# Main_V3.net
KiCad netlist of a schematic drawn in EAGLE
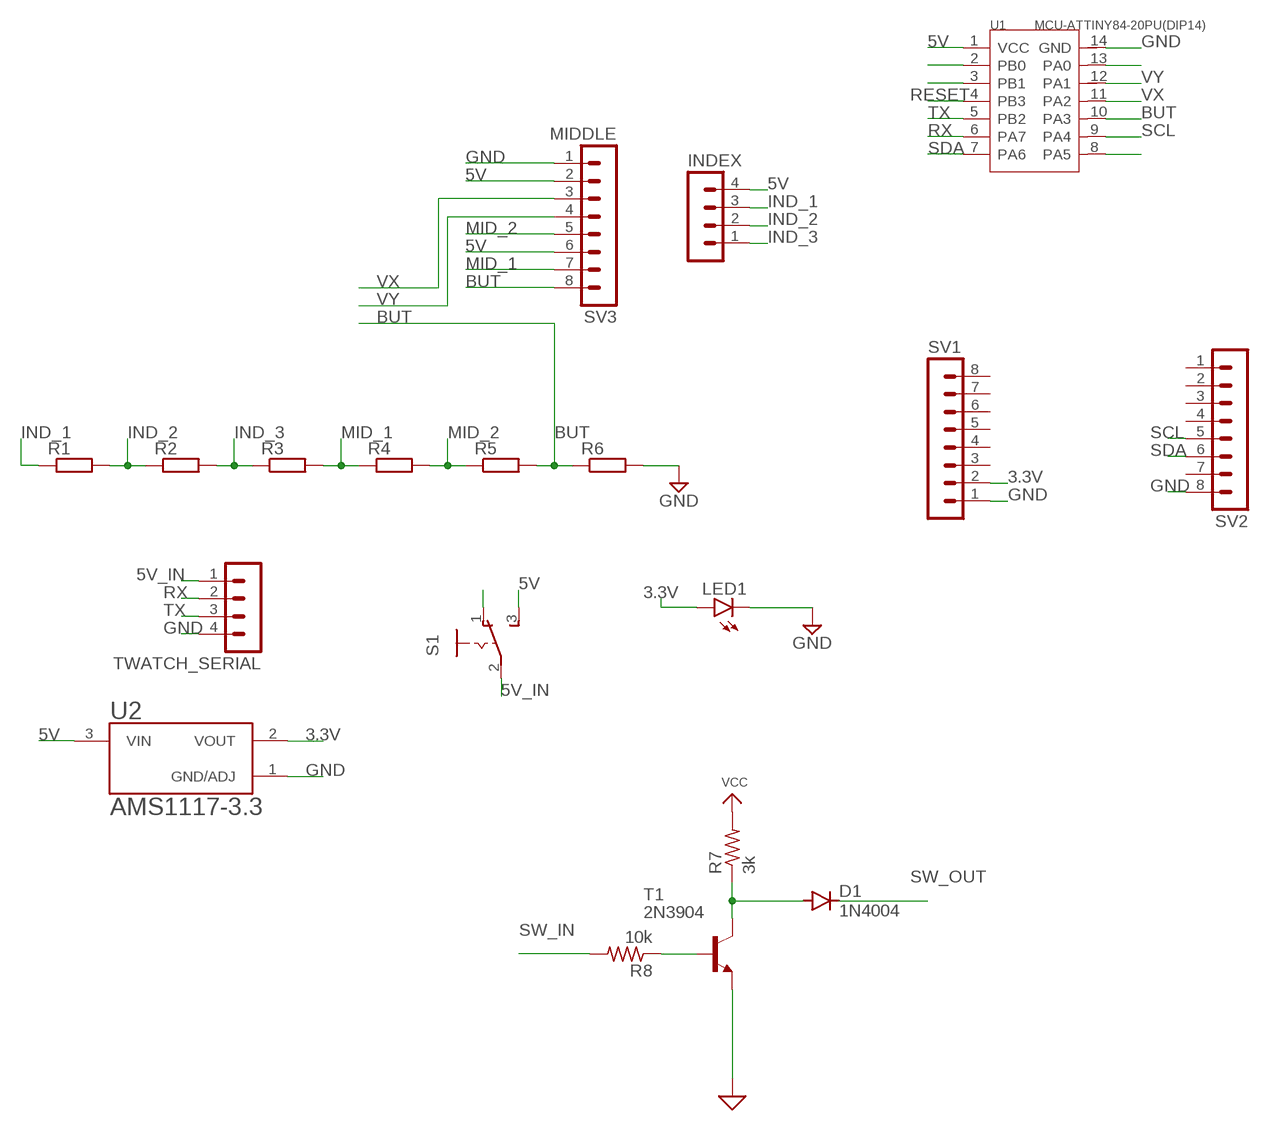
[diagram p0: schematic, sheet 1]

(export (version "E")
  (design (tool "Eeschema 10.0.6"))
  (components
    (comp (ref "D1")
      (value "1N4004")
      (footprint "eagle-import:DO41-10")
      (libsource (lib "eagle-import") (part "1N4004"))
    )
    (comp (ref "INDEX")
      (value "MA04-1")
      (footprint "eagle-import:MA04-1")
      (libsource (lib "eagle-import") (part "MA04-1"))
    )
    (comp (ref "LED1")
      (value "LED5MM")
      (footprint "eagle-import:LED5MM")
      (libsource (lib "eagle-import") (part "LED5MM"))
    )
    (comp (ref "R1")
      (value "R-EU_0204/7")
      (footprint "eagle-import:0204_7")
      (libsource (lib "eagle-import") (part "R-EU_0204/7"))
    )
    (comp (ref "R2")
      (value "R-EU_0204/7")
      (footprint "eagle-import:0204_7")
      (libsource (lib "eagle-import") (part "R-EU_0204/7"))
    )
    (comp (ref "R3")
      (value "R-EU_0204/7")
      (footprint "eagle-import:0204_7")
      (libsource (lib "eagle-import") (part "R-EU_0204/7"))
    )
    (comp (ref "R4")
      (value "R-EU_0204/7")
      (footprint "eagle-import:0204_7")
      (libsource (lib "eagle-import") (part "R-EU_0204/7"))
    )
    (comp (ref "R5")
      (value "R-EU_0204/7")
      (footprint "eagle-import:0204_7")
      (libsource (lib "eagle-import") (part "R-EU_0204/7"))
    )
    (comp (ref "R6")
      (value "R-EU_0204/7")
      (footprint "eagle-import:0204_7")
      (libsource (lib "eagle-import") (part "R-EU_0204/7"))
    )
    (comp (ref "R7")
      (value "3k")
      (footprint "eagle-import:0204_5")
      (libsource (lib "eagle-import") (part "R-US_0204/5"))
    )
    (comp (ref "R8")
      (value "10k")
      (footprint "eagle-import:0204_5")
      (libsource (lib "eagle-import") (part "R-US_0204/5"))
    )
    (comp (ref "S1")
      (value "255SB")
      (footprint "eagle-import:255SB")
      (libsource (lib "eagle-import") (part "255SB"))
    )
    (comp (ref "SV1")
      (value "MA08-1")
      (footprint "eagle-import:MA08-1")
      (libsource (lib "eagle-import") (part "MA08-1"))
    )
    (comp (ref "SV2")
      (value "MA08-1")
      (footprint "eagle-import:MA08-1")
      (libsource (lib "eagle-import") (part "MA08-1"))
    )
    (comp (ref "SV3")
      (value "MIDDLE")
      (footprint "eagle-import:MA08-1")
      (libsource (lib "eagle-import") (part "MA08-1"))
    )
    (comp (ref "T1")
      (value "2N3904")
      (footprint "eagle-import:TO92")
      (libsource (lib "eagle-import") (part "2N3904"))
    )
    (comp (ref "TWATCH_SERIAL")
      (value "MA04-1")
      (footprint "eagle-import:MA04-1")
      (libsource (lib "eagle-import") (part "MA04-1"))
    )
    (comp (ref "U1")
      (value "MCU-ATTINY84-20PU(DIP14)")
      (footprint "eagle-import:DIP14-2.54-17.24X6.35MM")
      (fields (field (name "MF") "Microchip") (field (name "MP") "ATTINY84-20PU"))
      (libsource (lib "eagle-import") (part "MCU-ATTINY84-20PU(DIP14)"))
    )
    (comp (ref "U2")
      (value "AMS1117-3.3")
      (footprint "eagle-import:SOT229P700X180-4N")
      (fields (field (name "MF") "Advanced Monolithic Systems"))
      (libsource (lib "eagle-import") (part "AMS1117-3.3"))
    )
  )
  (nets
    (net (code "1") (name "/3.3V") (class "Default")
      (node (ref "LED1") (pin "A") (pinfunction "A_A") (pintype "passive"))
      (node (ref "SV1") (pin "2") (pinfunction "2_2") (pintype "passive"))
      (node (ref "U2") (pin "2") (pinfunction "VOUT_2") (pintype "output"))
    )
    (net (code "2") (name "/5V") (class "Default")
      (node (ref "INDEX") (pin "4") (pinfunction "4_4") (pintype "passive"))
      (node (ref "S1") (pin "3") (pinfunction "S_3") (pintype "passive"))
      (node (ref "SV3") (pin "2") (pinfunction "2_2") (pintype "passive"))
      (node (ref "SV3") (pin "6") (pinfunction "6_6") (pintype "passive"))
      (node (ref "U1") (pin "1") (pinfunction "VCC_1") (pintype "bidirectional"))
      (node (ref "U2") (pin "3") (pinfunction "VIN_3") (pintype "input"))
    )
    (net (code "3") (name "/5V_IN") (class "Default")
      (node (ref "S1") (pin "2") (pinfunction "P_2") (pintype "passive"))
      (node (ref "TWATCH_SERIAL") (pin "1") (pinfunction "1_1") (pintype "passive"))
    )
    (net (code "4") (name "/BUT") (class "Default")
      (node (ref "R5") (pin "2") (pinfunction "2_2") (pintype "passive"))
      (node (ref "R6") (pin "1") (pinfunction "1_1") (pintype "passive"))
      (node (ref "SV3") (pin "8") (pinfunction "8_8") (pintype "passive"))
      (node (ref "U1") (pin "10") (pinfunction "PA3_10") (pintype "bidirectional"))
    )
    (net (code "5") (name "/IND_1") (class "Default")
      (node (ref "INDEX") (pin "3") (pinfunction "3_3") (pintype "passive"))
      (node (ref "R1") (pin "1") (pinfunction "1_1") (pintype "passive"))
    )
    (net (code "6") (name "/IND_2") (class "Default")
      (node (ref "INDEX") (pin "2") (pinfunction "2_2") (pintype "passive"))
      (node (ref "R1") (pin "2") (pinfunction "2_2") (pintype "passive"))
      (node (ref "R2") (pin "1") (pinfunction "1_1") (pintype "passive"))
    )
    (net (code "7") (name "/IND_3") (class "Default")
      (node (ref "INDEX") (pin "1") (pinfunction "1_1") (pintype "passive"))
      (node (ref "R2") (pin "2") (pinfunction "2_2") (pintype "passive"))
      (node (ref "R3") (pin "1") (pinfunction "1_1") (pintype "passive"))
    )
    (net (code "8") (name "/MID_1") (class "Default")
      (node (ref "R3") (pin "2") (pinfunction "2_2") (pintype "passive"))
      (node (ref "R4") (pin "1") (pinfunction "1_1") (pintype "passive"))
      (node (ref "SV3") (pin "7") (pinfunction "7_7") (pintype "passive"))
    )
    (net (code "9") (name "/MID_2") (class "Default")
      (node (ref "R4") (pin "2") (pinfunction "2_2") (pintype "passive"))
      (node (ref "R5") (pin "1") (pinfunction "1_1") (pintype "passive"))
      (node (ref "SV3") (pin "5") (pinfunction "5_5") (pintype "passive"))
    )
    (net (code "10") (name "/RESET") (class "Default")
      (node (ref "U1") (pin "4") (pinfunction "PB3_4") (pintype "bidirectional"))
    )
    (net (code "11") (name "/RX") (class "Default")
      (node (ref "TWATCH_SERIAL") (pin "2") (pinfunction "2_2") (pintype "passive"))
      (node (ref "U1") (pin "6") (pinfunction "PA7_6") (pintype "bidirectional"))
    )
    (net (code "12") (name "/SCL") (class "Default")
      (node (ref "SV2") (pin "5") (pinfunction "5_5") (pintype "passive"))
      (node (ref "U1") (pin "9") (pinfunction "PA4_9") (pintype "bidirectional"))
    )
    (net (code "13") (name "/SDA") (class "Default")
      (node (ref "SV2") (pin "6") (pinfunction "6_6") (pintype "passive"))
      (node (ref "U1") (pin "7") (pinfunction "PA6_7") (pintype "bidirectional"))
    )
    (net (code "14") (name "/SW_IN") (class "Default")
      (node (ref "R8") (pin "2") (pinfunction "2_2") (pintype "passive"))
    )
    (net (code "15") (name "/SW_OUT") (class "Default")
      (node (ref "D1") (pin "C") (pinfunction "C_C") (pintype "passive"))
    )
    (net (code "16") (name "/TX") (class "Default")
      (node (ref "TWATCH_SERIAL") (pin "3") (pinfunction "3_3") (pintype "passive"))
      (node (ref "U1") (pin "5") (pinfunction "PB2_5") (pintype "bidirectional"))
    )
    (net (code "17") (name "/VX") (class "Default")
      (node (ref "SV3") (pin "3") (pinfunction "3_3") (pintype "passive"))
      (node (ref "U1") (pin "11") (pinfunction "PA2_11") (pintype "bidirectional"))
    )
    (net (code "18") (name "/VY") (class "Default")
      (node (ref "SV3") (pin "4") (pinfunction "4_4") (pintype "passive"))
      (node (ref "U1") (pin "12") (pinfunction "PA1_12") (pintype "bidirectional"))
    )
    (net (code "19") (name "GND") (class "Default")
      (node (ref "LED1") (pin "K") (pinfunction "C_K") (pintype "passive"))
      (node (ref "R6") (pin "2") (pinfunction "2_2") (pintype "passive"))
      (node (ref "SV1") (pin "1") (pinfunction "1_1") (pintype "passive"))
      (node (ref "SV2") (pin "8") (pinfunction "8_8") (pintype "passive"))
      (node (ref "SV3") (pin "1") (pinfunction "1_1") (pintype "passive"))
      (node (ref "T1") (pin "3") (pinfunction "E_3") (pintype "passive"))
      (node (ref "TWATCH_SERIAL") (pin "4") (pinfunction "4_4") (pintype "passive"))
      (node (ref "U1") (pin "14") (pinfunction "GND_14") (pintype "bidirectional"))
      (node (ref "U2") (pin "1") (pinfunction "GND/ADJ_1") (pintype "power_in"))
    )
    (net (code "20") (name "Net-(T1-B)") (class "Default")
      (node (ref "R8") (pin "1") (pinfunction "1_1") (pintype "passive"))
      (node (ref "T1") (pin "2") (pinfunction "B_2") (pintype "passive"))
    )
    (net (code "21") (name "Net-(T1-C)") (class "Default")
      (node (ref "D1") (pin "A") (pinfunction "A_A") (pintype "passive"))
      (node (ref "R7") (pin "1") (pinfunction "1_1") (pintype "passive"))
      (node (ref "T1") (pin "1") (pinfunction "C_1") (pintype "passive"))
    )
    (net (code "22") (name "VCC") (class "Default")
      (node (ref "R7") (pin "2") (pinfunction "2_2") (pintype "passive"))
    )
    (net (code "23") (name "unconnected-(S1-O-Pad1)") (class "Default")
      (node (ref "S1") (pin "1") (pinfunction "O_1") (pintype "passive"))
    )
    (net (code "24") (name "unconnected-(SV1-Pad3)") (class "Default")
      (node (ref "SV1") (pin "3") (pinfunction "3_3") (pintype "passive"))
    )
    (net (code "25") (name "unconnected-(SV1-Pad4)") (class "Default")
      (node (ref "SV1") (pin "4") (pinfunction "4_4") (pintype "passive"))
    )
    (net (code "26") (name "unconnected-(SV1-Pad5)") (class "Default")
      (node (ref "SV1") (pin "5") (pinfunction "5_5") (pintype "passive"))
    )
    (net (code "27") (name "unconnected-(SV1-Pad6)") (class "Default")
      (node (ref "SV1") (pin "6") (pinfunction "6_6") (pintype "passive"))
    )
    (net (code "28") (name "unconnected-(SV1-Pad7)") (class "Default")
      (node (ref "SV1") (pin "7") (pinfunction "7_7") (pintype "passive"))
    )
    (net (code "29") (name "unconnected-(SV1-Pad8)") (class "Default")
      (node (ref "SV1") (pin "8") (pinfunction "8_8") (pintype "passive"))
    )
    (net (code "30") (name "unconnected-(SV2-Pad1)") (class "Default")
      (node (ref "SV2") (pin "1") (pinfunction "1_1") (pintype "passive"))
    )
    (net (code "31") (name "unconnected-(SV2-Pad2)") (class "Default")
      (node (ref "SV2") (pin "2") (pinfunction "2_2") (pintype "passive"))
    )
    (net (code "32") (name "unconnected-(SV2-Pad3)") (class "Default")
      (node (ref "SV2") (pin "3") (pinfunction "3_3") (pintype "passive"))
    )
    (net (code "33") (name "unconnected-(SV2-Pad4)") (class "Default")
      (node (ref "SV2") (pin "4") (pinfunction "4_4") (pintype "passive"))
    )
    (net (code "34") (name "unconnected-(SV2-Pad7)") (class "Default")
      (node (ref "SV2") (pin "7") (pinfunction "7_7") (pintype "passive"))
    )
    (net (code "35") (name "unconnected-(U1-PA0-Pad13)") (class "Default")
      (node (ref "U1") (pin "13") (pinfunction "PA0_13") (pintype "bidirectional"))
    )
    (net (code "36") (name "unconnected-(U1-PA5-Pad8)") (class "Default")
      (node (ref "U1") (pin "8") (pinfunction "PA5_8") (pintype "bidirectional"))
    )
    (net (code "37") (name "unconnected-(U1-PB0-Pad2)") (class "Default")
      (node (ref "U1") (pin "2") (pinfunction "PB0_2") (pintype "bidirectional"))
    )
    (net (code "38") (name "unconnected-(U1-PB1-Pad3)") (class "Default")
      (node (ref "U1") (pin "3") (pinfunction "PB1_3") (pintype "bidirectional"))
    )
  )
)
